# esquematico_inicial_para_a_FRMF.net
KiCad netlist of a schematic drawn in EAGLE
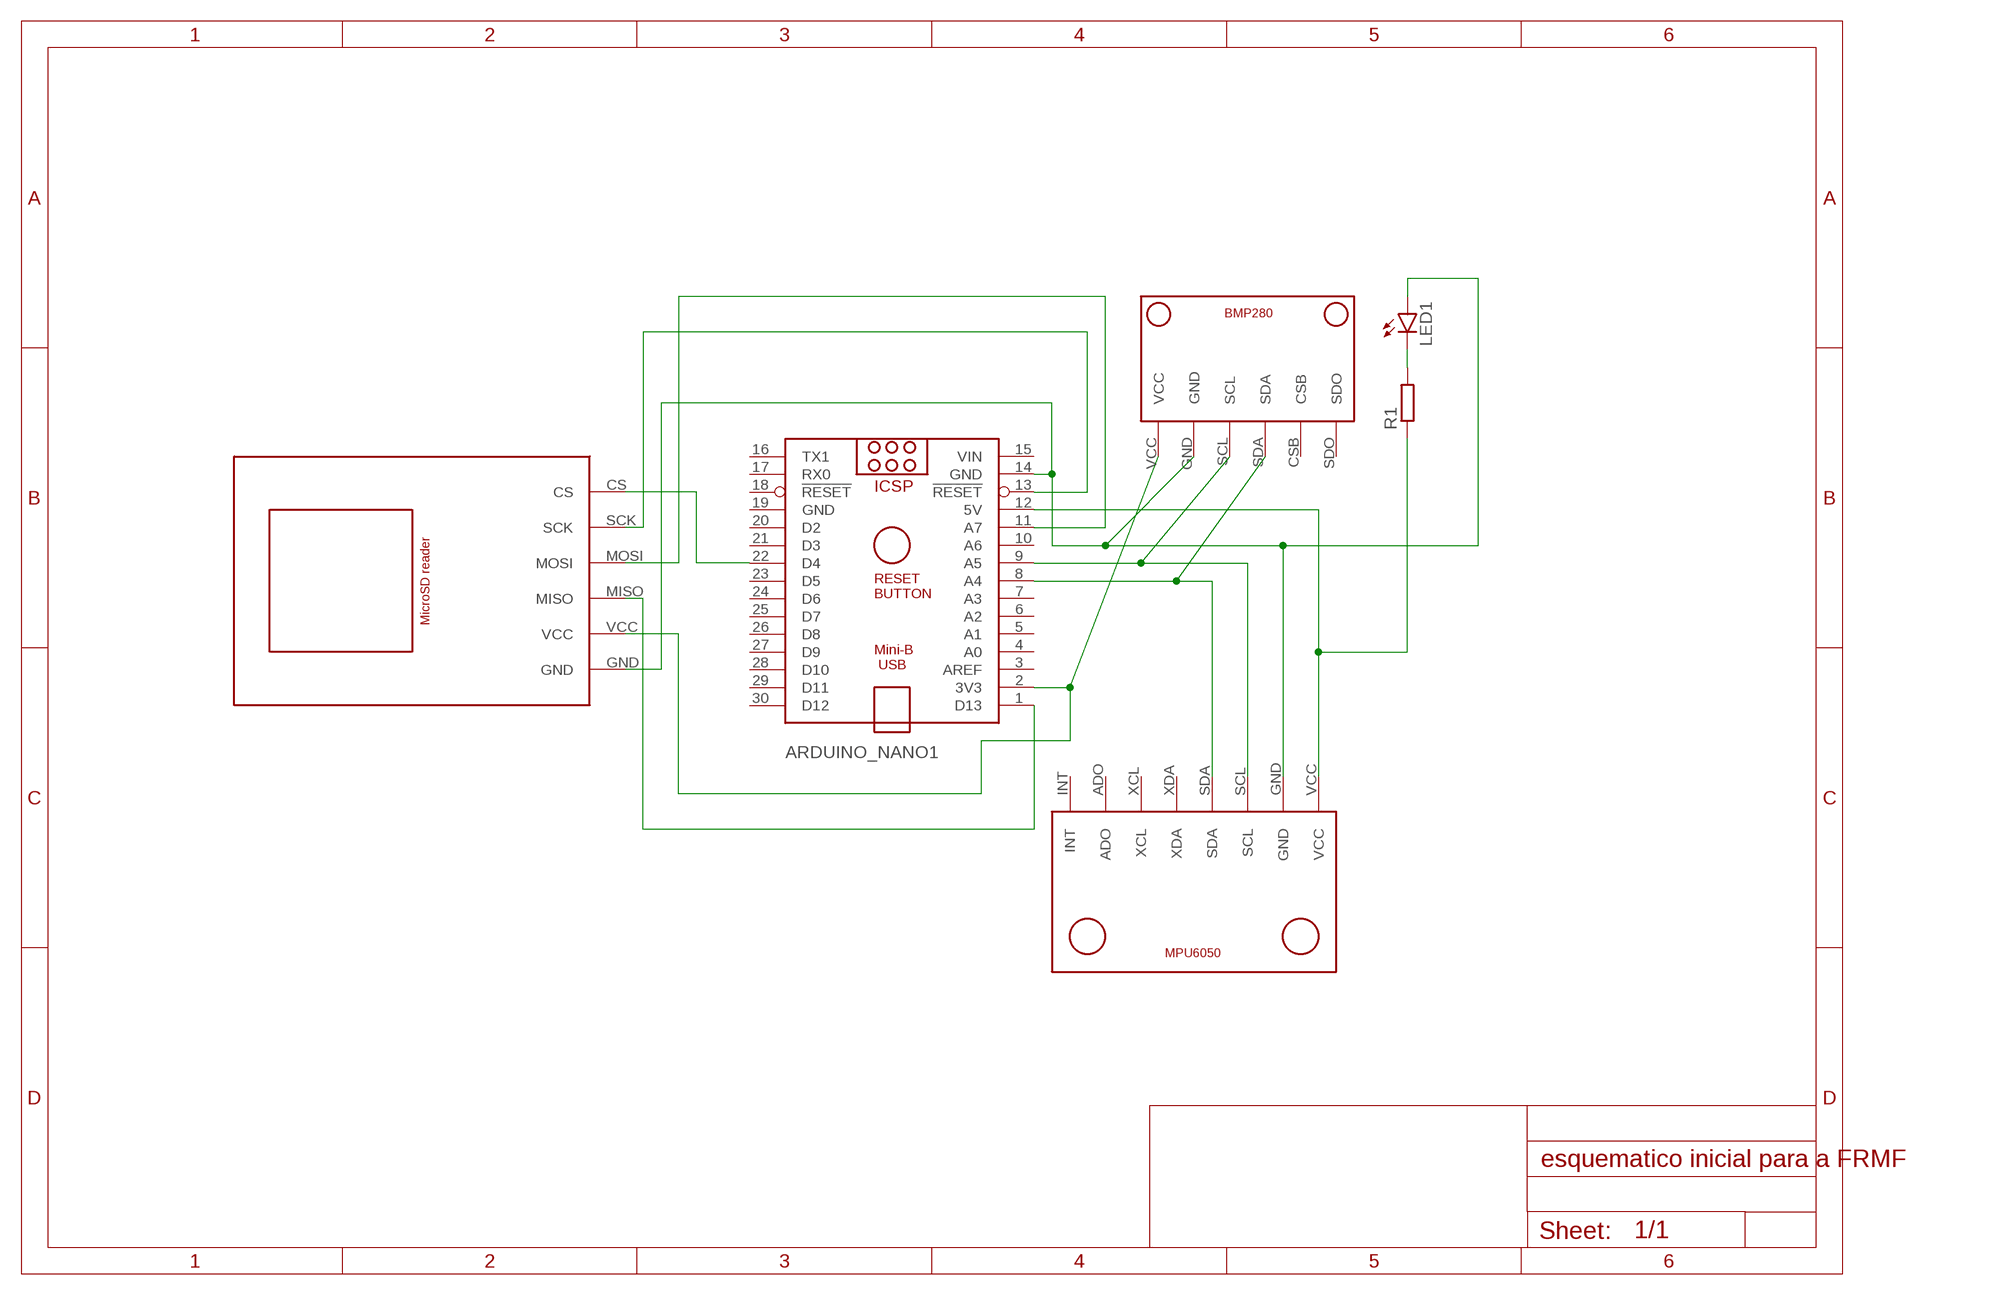
[diagram p0: schematic, sheet 1]

(export (version "E")
  (design (tool "Eeschema 10.0.6"))
  (components
    (comp (ref "ARDUINO_NANO1")
      (value "ARDUINO_NANO")
      (footprint "eagle-import:ARDUINO_NANO")
      (libsource (lib "eagle-import") (part "ARDUINO_NANO"))
    )
    (comp (ref "LED1")
      (value "LED5MM")
      (footprint "eagle-import:LED5MM")
      (libsource (lib "eagle-import") (part "LED5MM"))
    )
    (comp (ref "R1")
      (value "R-EU_0207/10")
      (footprint "eagle-import:0207_10")
      (libsource (lib "eagle-import") (part "R-EU_0207/10"))
    )
    (comp (ref "U$1")
      (value "BMP280V1")
      (footprint "eagle-import:BMP280_FOOTPRINT")
      (libsource (lib "eagle-import") (part "BMP280V1"))
    )
    (comp (ref "U$2")
      (value "MPU6050V1")
      (footprint "eagle-import:MPU6050_FOOTPRINT")
      (libsource (lib "eagle-import") (part "MPU6050V1"))
    )
    (comp (ref "U$3")
      (value "MICROSD_READER")
      (footprint "eagle-import:MICROSD_READER_FOOTPRINT")
      (libsource (lib "eagle-import") (part "MICROSD_READER"))
    )
  )
  (nets
    (net (code "1") (name "/GND") (class "Default")
      (node (ref "ARDUINO_NANO1") (pin "19") (pinfunction "GND_19") (pintype "power_in"))
    )
    (net (code "2") (name "/VIN") (class "Default")
      (node (ref "ARDUINO_NANO1") (pin "15") (pinfunction "VIN_15") (pintype "power_in"))
    )
    (net (code "3") (name "Net-(ARDUINO_NANO1-3V3)") (class "Default")
      (node (ref "ARDUINO_NANO1") (pin "2") (pinfunction "3V3_2") (pintype "output"))
      (node (ref "U$1") (pin "VCC") (pinfunction "VCC_VCC") (pintype "bidirectional"))
      (node (ref "U$3") (pin "VCC") (pinfunction "VCC_VCC") (pintype "bidirectional"))
    )
    (net (code "4") (name "Net-(ARDUINO_NANO1-5V)") (class "Default")
      (node (ref "ARDUINO_NANO1") (pin "12") (pinfunction "5V_12") (pintype "power_in"))
      (node (ref "R1") (pin "1") (pinfunction "1_1") (pintype "passive"))
      (node (ref "U$2") (pin "VCC") (pinfunction "VCC_VCC") (pintype "bidirectional"))
    )
    (net (code "5") (name "Net-(ARDUINO_NANO1-A4)") (class "Default")
      (node (ref "ARDUINO_NANO1") (pin "8") (pinfunction "A4_8") (pintype "bidirectional"))
      (node (ref "U$1") (pin "SDA") (pinfunction "SDA_SDA") (pintype "bidirectional"))
      (node (ref "U$2") (pin "SDA") (pinfunction "SDA_SDA") (pintype "bidirectional"))
    )
    (net (code "6") (name "Net-(ARDUINO_NANO1-A5)") (class "Default")
      (node (ref "ARDUINO_NANO1") (pin "9") (pinfunction "A5_9") (pintype "bidirectional"))
      (node (ref "U$1") (pin "SCL") (pinfunction "SCL_SCL") (pintype "bidirectional"))
      (node (ref "U$2") (pin "SCL") (pinfunction "SCL_SCL") (pintype "bidirectional"))
    )
    (net (code "7") (name "Net-(ARDUINO_NANO1-A7)") (class "Default")
      (node (ref "ARDUINO_NANO1") (pin "11") (pinfunction "A7_11") (pintype "bidirectional"))
      (node (ref "U$3") (pin "MOSI") (pinfunction "MOSI_MOSI") (pintype "bidirectional"))
    )
    (net (code "8") (name "Net-(ARDUINO_NANO1-D4)") (class "Default")
      (node (ref "ARDUINO_NANO1") (pin "22") (pinfunction "D4_22") (pintype "bidirectional"))
      (node (ref "U$3") (pin "CS") (pinfunction "CS_CS") (pintype "bidirectional"))
    )
    (net (code "9") (name "Net-(ARDUINO_NANO1-D13)") (class "Default")
      (node (ref "ARDUINO_NANO1") (pin "1") (pinfunction "D13_1") (pintype "bidirectional"))
      (node (ref "U$3") (pin "MISO") (pinfunction "MISO_MISO") (pintype "bidirectional"))
    )
    (net (code "10") (name "Net-(ARDUINO_NANO1-GND-Pad14)") (class "Default")
      (node (ref "ARDUINO_NANO1") (pin "14") (pinfunction "GND_14") (pintype "power_in"))
      (node (ref "LED1") (pin "A") (pinfunction "A_A") (pintype "passive"))
      (node (ref "U$1") (pin "GND") (pinfunction "GND_GND") (pintype "bidirectional"))
      (node (ref "U$2") (pin "GND") (pinfunction "GND_GND") (pintype "bidirectional"))
      (node (ref "U$3") (pin "GND") (pinfunction "GND_GND") (pintype "bidirectional"))
    )
    (net (code "11") (name "Net-(ARDUINO_NANO1-~{RESET}-Pad13)") (class "Default")
      (node (ref "ARDUINO_NANO1") (pin "13") (pinfunction "~{RESET}_13") (pintype "input"))
      (node (ref "U$3") (pin "SCK") (pinfunction "SCK_SCK") (pintype "bidirectional"))
    )
    (net (code "12") (name "Net-(LED1-C)") (class "Default")
      (node (ref "LED1") (pin "K") (pinfunction "C_K") (pintype "passive"))
      (node (ref "R1") (pin "2") (pinfunction "2_2") (pintype "passive"))
    )
    (net (code "13") (name "unconnected-(ARDUINO_NANO1-A0-Pad4)") (class "Default")
      (node (ref "ARDUINO_NANO1") (pin "4") (pinfunction "A0_4") (pintype "bidirectional"))
    )
    (net (code "14") (name "unconnected-(ARDUINO_NANO1-A1-Pad5)") (class "Default")
      (node (ref "ARDUINO_NANO1") (pin "5") (pinfunction "A1_5") (pintype "bidirectional"))
    )
    (net (code "15") (name "unconnected-(ARDUINO_NANO1-A2-Pad6)") (class "Default")
      (node (ref "ARDUINO_NANO1") (pin "6") (pinfunction "A2_6") (pintype "bidirectional"))
    )
    (net (code "16") (name "unconnected-(ARDUINO_NANO1-A3-Pad7)") (class "Default")
      (node (ref "ARDUINO_NANO1") (pin "7") (pinfunction "A3_7") (pintype "bidirectional"))
    )
    (net (code "17") (name "unconnected-(ARDUINO_NANO1-A6-Pad10)") (class "Default")
      (node (ref "ARDUINO_NANO1") (pin "10") (pinfunction "A6_10") (pintype "bidirectional"))
    )
    (net (code "18") (name "unconnected-(ARDUINO_NANO1-AREF-Pad3)") (class "Default")
      (node (ref "ARDUINO_NANO1") (pin "3") (pinfunction "AREF_3") (pintype "input"))
    )
    (net (code "19") (name "unconnected-(ARDUINO_NANO1-D2-Pad20)") (class "Default")
      (node (ref "ARDUINO_NANO1") (pin "20") (pinfunction "D2_20") (pintype "bidirectional"))
    )
    (net (code "20") (name "unconnected-(ARDUINO_NANO1-D3-Pad21)") (class "Default")
      (node (ref "ARDUINO_NANO1") (pin "21") (pinfunction "D3_21") (pintype "bidirectional"))
    )
    (net (code "21") (name "unconnected-(ARDUINO_NANO1-D5-Pad23)") (class "Default")
      (node (ref "ARDUINO_NANO1") (pin "23") (pinfunction "D5_23") (pintype "bidirectional"))
    )
    (net (code "22") (name "unconnected-(ARDUINO_NANO1-D6-Pad24)") (class "Default")
      (node (ref "ARDUINO_NANO1") (pin "24") (pinfunction "D6_24") (pintype "bidirectional"))
    )
    (net (code "23") (name "unconnected-(ARDUINO_NANO1-D7-Pad25)") (class "Default")
      (node (ref "ARDUINO_NANO1") (pin "25") (pinfunction "D7_25") (pintype "bidirectional"))
    )
    (net (code "24") (name "unconnected-(ARDUINO_NANO1-D8-Pad26)") (class "Default")
      (node (ref "ARDUINO_NANO1") (pin "26") (pinfunction "D8_26") (pintype "bidirectional"))
    )
    (net (code "25") (name "unconnected-(ARDUINO_NANO1-D9-Pad27)") (class "Default")
      (node (ref "ARDUINO_NANO1") (pin "27") (pinfunction "D9_27") (pintype "bidirectional"))
    )
    (net (code "26") (name "unconnected-(ARDUINO_NANO1-D10-Pad28)") (class "Default")
      (node (ref "ARDUINO_NANO1") (pin "28") (pinfunction "D10_28") (pintype "bidirectional"))
    )
    (net (code "27") (name "unconnected-(ARDUINO_NANO1-D11-Pad29)") (class "Default")
      (node (ref "ARDUINO_NANO1") (pin "29") (pinfunction "D11_29") (pintype "bidirectional"))
    )
    (net (code "28") (name "unconnected-(ARDUINO_NANO1-D12-Pad30)") (class "Default")
      (node (ref "ARDUINO_NANO1") (pin "30") (pinfunction "D12_30") (pintype "bidirectional"))
    )
    (net (code "29") (name "unconnected-(ARDUINO_NANO1-RX0-Pad17)") (class "Default")
      (node (ref "ARDUINO_NANO1") (pin "17") (pinfunction "RX0_17") (pintype "bidirectional"))
    )
    (net (code "30") (name "unconnected-(ARDUINO_NANO1-TX1-Pad16)") (class "Default")
      (node (ref "ARDUINO_NANO1") (pin "16") (pinfunction "TX1_16") (pintype "bidirectional"))
    )
    (net (code "31") (name "unconnected-(ARDUINO_NANO1-~{RESET}-Pad18)") (class "Default")
      (node (ref "ARDUINO_NANO1") (pin "18") (pinfunction "~{RESET}_18") (pintype "input"))
    )
    (net (code "32") (name "unconnected-(U$1-PadCSB)") (class "Default")
      (node (ref "U$1") (pin "CSB") (pinfunction "CSB_CSB") (pintype "bidirectional"))
    )
    (net (code "33") (name "unconnected-(U$1-PadSDO)") (class "Default")
      (node (ref "U$1") (pin "SDO") (pinfunction "SDO_SDO") (pintype "bidirectional"))
    )
    (net (code "34") (name "unconnected-(U$2-PadADO)") (class "Default")
      (node (ref "U$2") (pin "ADO") (pinfunction "ADO_ADO") (pintype "bidirectional"))
    )
    (net (code "35") (name "unconnected-(U$2-PadINT)") (class "Default")
      (node (ref "U$2") (pin "INT") (pinfunction "INT_INT") (pintype "bidirectional"))
    )
    (net (code "36") (name "unconnected-(U$2-PadXCL)") (class "Default")
      (node (ref "U$2") (pin "XCL") (pinfunction "XCL_XCL") (pintype "bidirectional"))
    )
    (net (code "37") (name "unconnected-(U$2-PadXDA)") (class "Default")
      (node (ref "U$2") (pin "XDA") (pinfunction "XDA_XDA") (pintype "bidirectional"))
    )
  )
)
